# SCH_claprelay_2025-04-26.net
KiCad netlist of a schematic drawn in EasyEDA
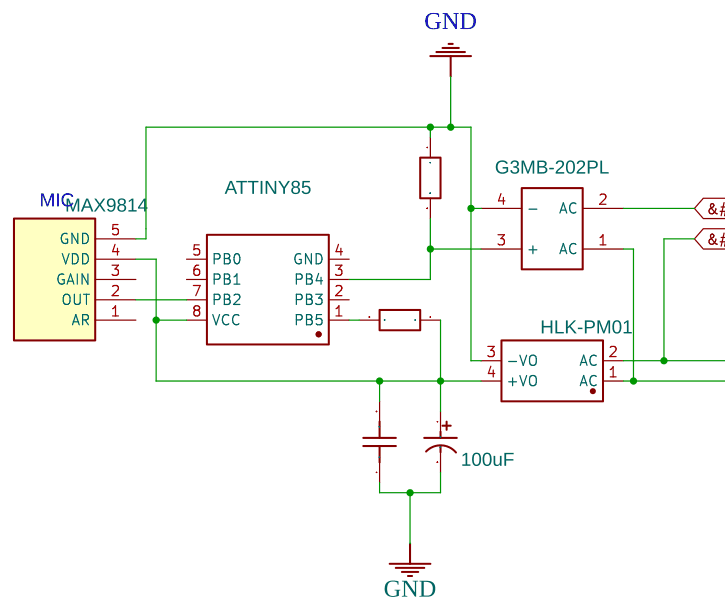
[diagram p0: schematic sheet]

(export (version "E")
  (design (tool "Eeschema 10.0.6"))
  (components
    (comp (ref "C3")
      (value "100nF")
      (fields
        (field (name "Manufacturer Part") "RDER71E104K0M1H03A")
        (field (name "Manufacturer") "muRata(村田)")
      )
      (libsource (lib "") (part "RDER71E104K0M1H03A"))
    )
    (comp (ref "C4")
      (value "100uF")
      (fields (field (name "Manufacturer Part") "KF101M016C110A") (field (name "Manufacturer") "CapXon"))
      (libsource (lib "") (part "KF101M016C110A"))
    )
    (comp (ref "K2")
      (value "G3MB-202PL")
      (fields (field (name "Manufacturer") "OMRON"))
      (libsource (lib "") (part "G3MB-202PL"))
    )
    (comp (ref "R3")
      (value "10k")
      (fields
        (field (name "Manufacturer Part") "MF1/4W-470KΩ±1%T52")
        (field (name "Manufacturer") "Huaxing Mechanical-Elec.")
      )
      (libsource (lib "") (part "MF1/4W-470KΩ±1%T52_1"))
    )
    (comp (ref "R4")
      (value "10k")
      (fields
        (field (name "Manufacturer Part") "MF1/4W-470KΩ±1%T52")
        (field (name "Manufacturer") "Huaxing Mechanical-Elec.")
      )
      (libsource (lib "") (part "MF1/4W-470KΩ±1%T52"))
    )
    (comp (ref "U4") (value "MAX9814") (libsource (lib "") (part "MAX9814 MODULE")))
    (comp (ref "U6")
      (value "HLK-PM01")
      (fields (field (name "Manufacturer") "HI-LINK"))
      (libsource (lib "") (part "HLK-PM01"))
    )
    (comp (ref "U7")
      (value "ATTINY85")
      (fields
        (field (name "Manufacturer Part") "ATTINY85V-10SUR")
        (field (name "Manufacturer") "MICROCHIP(美国微芯)")
      )
      (libsource (lib "") (part "ATTINY85V-10SUR"))
    )
  )
  (nets
    (net (code "1") (name "&#126;220V-0") (class "Default")
      (node (ref "U6") (pin "2") (pinfunction "AC_2") (pintype "unspecified"))
    )
    (net (code "2") (name "&#126;220V-1") (class "Default")
      (node (ref "K2") (pin "1") (pinfunction "AC_1") (pintype "unspecified"))
      (node (ref "U6") (pin "1") (pinfunction "AC_1") (pintype "unspecified"))
    )
    (net (code "3") (name "&#126;LOAD0") (class "Default")
      (node (ref "K2") (pin "2") (pinfunction "AC_2") (pintype "unspecified"))
    )
    (net (code "4") (name "GND") (class "Default")
      (node (ref "C3") (pin "1") (pinfunction "1_1") (pintype "unspecified"))
      (node (ref "C4") (pin "2") (pinfunction "2_2") (pintype "input"))
      (node (ref "K2") (pin "4") (pinfunction "-_4") (pintype "unspecified"))
      (node (ref "R3") (pin "1") (pinfunction "1_1") (pintype "unspecified"))
      (node (ref "U4") (pin "5") (pinfunction "GND_5") (pintype "unspecified"))
      (node (ref "U6") (pin "3") (pinfunction "-VO_3") (pintype "unspecified"))
    )
    (net (code "5") (name "Net-(K2-+)") (class "Default")
      (node (ref "K2") (pin "3") (pinfunction "+_3") (pintype "unspecified"))
      (node (ref "R3") (pin "2") (pinfunction "2_2") (pintype "unspecified"))
      (node (ref "U7") (pin "3") (pinfunction "PB4_3") (pintype "unspecified"))
    )
    (net (code "6") (name "Net-(U4-OUT)") (class "Default")
      (node (ref "U4") (pin "2") (pinfunction "OUT_2") (pintype "unspecified"))
      (node (ref "U7") (pin "7") (pinfunction "PB2_7") (pintype "unspecified"))
    )
    (net (code "7") (name "Net-(U4-VDD)") (class "Default")
      (node (ref "C3") (pin "2") (pinfunction "2_2") (pintype "unspecified"))
      (node (ref "C4") (pin "1") (pinfunction "1_1") (pintype "input"))
      (node (ref "R4") (pin "1") (pinfunction "1_1") (pintype "unspecified"))
      (node (ref "U4") (pin "4") (pinfunction "VDD_4") (pintype "unspecified"))
      (node (ref "U6") (pin "4") (pinfunction "+VO_4") (pintype "unspecified"))
      (node (ref "U7") (pin "8") (pinfunction "VCC_8") (pintype "unspecified"))
    )
    (net (code "8") (name "Net-(U7-PB5)") (class "Default")
      (node (ref "R4") (pin "2") (pinfunction "2_2") (pintype "unspecified"))
      (node (ref "U7") (pin "1") (pinfunction "PB5_1") (pintype "unspecified"))
    )
    (net (code "9") (name "unconnected-(U4-AR-Pad1)") (class "Default")
      (node (ref "U4") (pin "1") (pinfunction "AR_1") (pintype "unspecified"))
    )
    (net (code "10") (name "unconnected-(U4-GAIN-Pad3)") (class "Default")
      (node (ref "U4") (pin "3") (pinfunction "GAIN_3") (pintype "unspecified"))
    )
    (net (code "11") (name "unconnected-(U7-GND-Pad4)") (class "Default")
      (node (ref "U7") (pin "4") (pinfunction "GND_4") (pintype "unspecified"))
    )
    (net (code "12") (name "unconnected-(U7-PB0-Pad5)") (class "Default")
      (node (ref "U7") (pin "5") (pinfunction "PB0_5") (pintype "unspecified"))
    )
    (net (code "13") (name "unconnected-(U7-PB1-Pad6)") (class "Default")
      (node (ref "U7") (pin "6") (pinfunction "PB1_6") (pintype "unspecified"))
    )
    (net (code "14") (name "unconnected-(U7-PB3-Pad2)") (class "Default")
      (node (ref "U7") (pin "2") (pinfunction "PB3_2") (pintype "unspecified"))
    )
  )
)
